# Schematics.net
KiCad netlist of a schematic drawn in Altium Designer
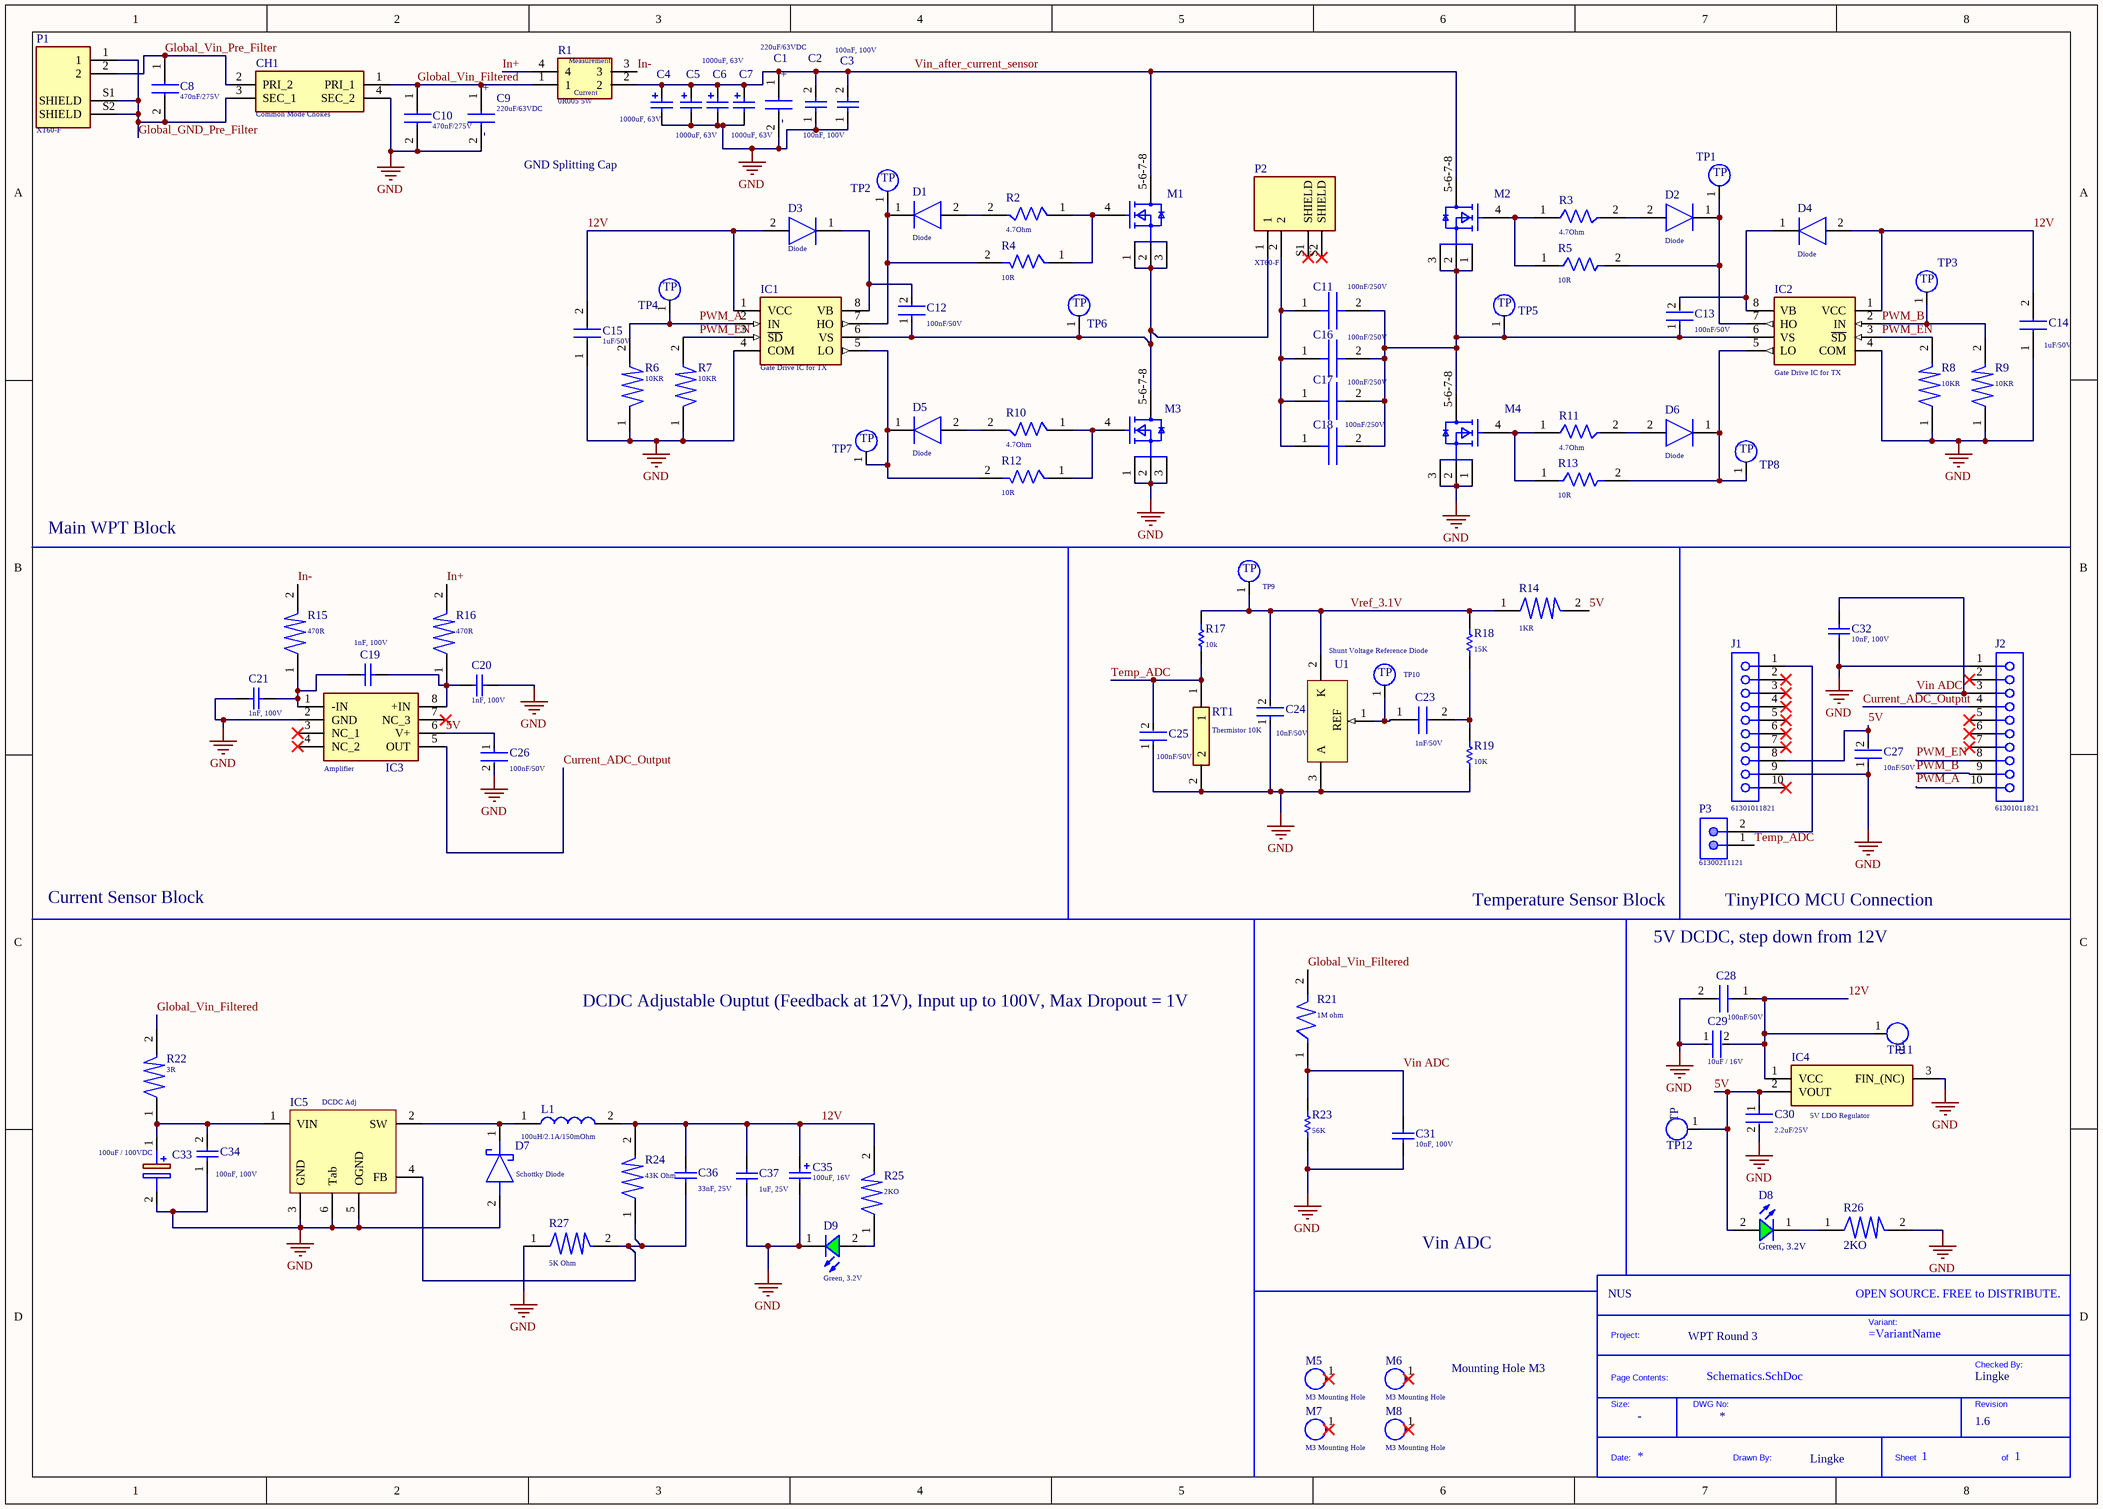
[diagram p0: Schematics.SchDoc]

(export (version "E")
  (design (tool "Eeschema 10.0.6"))
  (components
    (comp (ref "*1")
      (value "Title_Block")
      (description "Standard Title Block.")
      (fields
        (field (name "PROJECT NAME") "WPT Round 3")
        (field (name "COMPANY") "NUS")
        (field (name "DRAWN BY") "Lingke")
        (field (name "REVISION") "1.6")
        (field (name "DWG NO") "*")
        (field (name "SIZE") "-")
        (field (name "CHECKED BY") "Lingke")
      )
      (libsource (lib "Symbol Library") (part "Title_Block"))
    )
    (comp (ref "C1")
      (value "220uF/63VDC")
      (footprint "SamacSys:CAPPRD500W62D1000H2650")
      (description "Polarised Cap, 220uF/63VDC")
      (fields (field (name "MANUFACTURER_PART_NUMBER") "860040775010"))
      (libsource (lib "Symbol Library") (part "860040775010"))
    )
    (comp (ref "C2")
      (value "100nF, 100V")
      (footprint "WCAP-CSGP_0805_H=1.25mm")
      (description "WCAP-CSGP Multilayer Ceramic Chip Capacitor, General Purpose, size 0805, X7R, 100nF, 100V")
      (fields
        (field (name "MANUFACTURER PART NUMBER") "885012207128")
        (field (name "MANUFACTURER") "Wurth Elektronik")
      )
      (libsource (lib "Symbol Library") (part "885012207128"))
    )
    (comp (ref "C3")
      (value "100nF, 100V")
      (footprint "WCAP-CSGP_0805_H=1.25mm")
      (description "WCAP-CSGP Multilayer Ceramic Chip Capacitor, General Purpose, size 0805, X7R, 100nF, 100V")
      (fields
        (field (name "MANUFACTURER PART NUMBER") "885012207128")
        (field (name "MANUFACTURER") "Wurth Elektronik")
      )
      (libsource (lib "Symbol Library") (part "885012207128"))
    )
    (comp (ref "C4")
      (value "1000uF, 63V")
      (footprint "WCAP-ATG8_D16H25")
      (description "WCAP-ATG8 Aluminum Electrolytic Capacitor, Radial, THT, D16xH25, 1000uF, 63V")
      (fields
        (field (name "MANUFACTURER PART NUMBER") "860010780024")
        (field (name "MANUFACTURER") "Wurth Elektronik")
      )
      (libsource (lib "Altium_WCAP-ATG8 (rev20b)") (part "860010780024"))
    )
    (comp (ref "C5")
      (value "1000uF, 63V")
      (footprint "WCAP-ATG8_D16H25")
      (description "WCAP-ATG8 Aluminum Electrolytic Capacitor, Radial, THT, D16xH25, 1000uF, 63V")
      (fields
        (field (name "MANUFACTURER PART NUMBER") "860010780024")
        (field (name "MANUFACTURER") "Wurth Elektronik")
      )
      (libsource (lib "Altium_WCAP-ATG8 (rev20b)") (part "860010780024"))
    )
    (comp (ref "C6")
      (value "1000uF, 63V")
      (footprint "WCAP-ATG8_D16H25")
      (description "WCAP-ATG8 Aluminum Electrolytic Capacitor, Radial, THT, D16xH25, 1000uF, 63V")
      (fields
        (field (name "MANUFACTURER PART NUMBER") "860010780024")
        (field (name "MANUFACTURER") "Wurth Elektronik")
      )
      (libsource (lib "Altium_WCAP-ATG8 (rev20b)") (part "860010780024"))
    )
    (comp (ref "C7")
      (value "1000uF, 63V")
      (footprint "WCAP-ATG8_D16H25")
      (description "WCAP-ATG8 Aluminum Electrolytic Capacitor, Radial, THT, D16xH25, 1000uF, 63V")
      (fields
        (field (name "MANUFACTURER PART NUMBER") "860010780024")
        (field (name "MANUFACTURER") "Wurth Elektronik")
      )
      (libsource (lib "Altium_WCAP-ATG8 (rev20b)") (part "860010780024"))
    )
    (comp (ref "C8")
      (value "470nF/275V")
      (footprint "SamacSys:890324025039CS")
      (description "Safety Capacitor, 470nF/275V")
      (fields (field (name "MANUFACTURER_PART_NUMBER") "890324025039CS"))
      (libsource (lib "Symbol Library") (part "890324025039CS"))
    )
    (comp (ref "C9")
      (value "220uF/63VDC")
      (footprint "SamacSys:CAPPRD500W62D1000H2650")
      (description "Polarised Cap, 220uF/63VDC")
      (fields (field (name "MANUFACTURER_PART_NUMBER") "860040775010"))
      (libsource (lib "Symbol Library") (part "860040775010"))
    )
    (comp (ref "C10")
      (value "470nF/275V")
      (footprint "SamacSys:890324025039CS")
      (description "Safety Capacitor, 470nF/275V")
      (fields (field (name "MANUFACTURER_PART_NUMBER") "890324025039CS"))
      (libsource (lib "Symbol Library") (part "890324025039CS"))
    )
    (comp (ref "C11")
      (value "100nF/250V")
      (footprint "SamacSys:CAPC4532X220N")
      (fields (field (name "MANUFACTURER_PART_NUMBER") "C1812C104JAGACAUTO"))
      (libsource (lib "Symbol Library") (part "C1812C104JAGACAUTO"))
    )
    (comp (ref "C12")
      (value "100nF/50V")
      (footprint "0805 Capacitor")
      (libsource (lib "Symbol Library") (part "885012207098"))
    )
    (comp (ref "C13")
      (value "100nF/50V")
      (footprint "0805 Capacitor")
      (libsource (lib "Symbol Library") (part "885012207098"))
    )
    (comp (ref "C14")
      (value "1uF/50V")
      (footprint "SamacSys:CAPC2012X135N")
      (description "Capacitor 1uF/50V")
      (fields (field (name "MANUFACTURER_PART_NUMBER") "885012207103"))
      (libsource (lib "Symbol Library") (part "885012207103"))
    )
    (comp (ref "C15")
      (value "1uF/50V")
      (footprint "SamacSys:CAPC2012X135N")
      (description "Capacitor 1uF/50V")
      (fields (field (name "MANUFACTURER_PART_NUMBER") "885012207103"))
      (libsource (lib "Symbol Library") (part "885012207103"))
    )
    (comp (ref "C16")
      (value "100nF/250V")
      (footprint "SamacSys:CAPC4532X220N")
      (fields (field (name "MANUFACTURER_PART_NUMBER") "C1812C104JAGACAUTO"))
      (libsource (lib "Symbol Library") (part "C1812C104JAGACAUTO"))
    )
    (comp (ref "C17")
      (value "100nF/250V")
      (footprint "SamacSys:CAPC4532X220N")
      (fields (field (name "MANUFACTURER_PART_NUMBER") "C1812C104JAGACAUTO"))
      (libsource (lib "Symbol Library") (part "C1812C104JAGACAUTO"))
    )
    (comp (ref "C18")
      (value "100nF/250V")
      (footprint "SamacSys:CAPC4532X220N")
      (fields (field (name "MANUFACTURER_PART_NUMBER") "C1812C104JAGACAUTO"))
      (libsource (lib "Symbol Library") (part "C1812C104JAGACAUTO"))
    )
    (comp (ref "C19")
      (value "1nF, 100V")
      (footprint "WCAP-CSGP_0805_H=0.8mm_Reflow")
      (description "WCAP-CSGP Multilayer Ceramic Chip Capacitor, General Purpose, size 0805, X7R, 1nF, 100V")
      (fields
        (field (name "MANUFACTURER PART NUMBER") "885012207116")
        (field (name "MANUFACTURER") "Wurth Elektronik")
      )
      (libsource (lib "Altium_WCAP-CSGP (rev21d)") (part "885012207116"))
    )
    (comp (ref "C20")
      (value "1nF, 100V")
      (footprint "WCAP-CSGP_0805_H=0.8mm_Reflow")
      (description "WCAP-CSGP Multilayer Ceramic Chip Capacitor, General Purpose, size 0805, X7R, 1nF, 100V")
      (fields
        (field (name "MANUFACTURER PART NUMBER") "885012207116")
        (field (name "MANUFACTURER") "Wurth Elektronik")
      )
      (libsource (lib "Altium_WCAP-CSGP (rev21d)") (part "885012207116"))
    )
    (comp (ref "C21")
      (value "1nF, 100V")
      (footprint "WCAP-CSGP_0805_H=0.8mm_Reflow")
      (description "WCAP-CSGP Multilayer Ceramic Chip Capacitor, General Purpose, size 0805, X7R, 1nF, 100V")
      (fields
        (field (name "MANUFACTURER PART NUMBER") "885012207116")
        (field (name "MANUFACTURER") "Wurth Elektronik")
      )
      (libsource (lib "Altium_WCAP-CSGP (rev21d)") (part "885012207116"))
    )
    (comp (ref "C23")
      (value "1nF/50V")
      (footprint "SamacSys:CAPC2012X90N")
      (fields (field (name "MANUFACTURER_PART_NUMBER") "885012207086"))
      (libsource (lib "Symbol Library") (part "885012207086"))
    )
    (comp (ref "C24")
      (value "10nF/50V")
      (footprint "0805 Capacitor")
      (libsource (lib "Symbol Library") (part "885012207092"))
    )
    (comp (ref "C25")
      (value "100nF/50V")
      (footprint "0805 Capacitor")
      (libsource (lib "Symbol Library") (part "885012207098"))
    )
    (comp (ref "C26")
      (value "100nF/50V")
      (footprint "0805 Capacitor")
      (libsource (lib "Symbol Library") (part "885012207098"))
    )
    (comp (ref "C27")
      (value "10nF/50V")
      (footprint "0805 Capacitor")
      (libsource (lib "Symbol Library") (part "885012207092"))
    )
    (comp (ref "C28")
      (value "100nF/50V")
      (footprint "SamacSys:CAPC2012X90N")
      (libsource (lib "") (part "885012207098_1"))
    )
    (comp (ref "C29")
      (value "10uF / 16V")
      (footprint "0805 Capacitor")
      (description "100nF/50V")
      (libsource (lib "WPT NUS") (part "CL21A106KOQNNNE"))
    )
    (comp (ref "C30")
      (value "2.2uF/25V")
      (footprint "0805 Capacitor")
      (libsource (lib "Symbol Library") (part "885012207079"))
    )
    (comp (ref "C31")
      (value "10nF, 100V")
      (footprint "WCAP-CSGP_0805_H=0.8mm_Reflow")
      (description "WCAP-CSGP Multilayer Ceramic Chip Capacitor, General Purpose, size 0805, X7R, 10nF, 100V")
      (fields
        (field (name "MANUFACTURER PART NUMBER") "885012207122")
        (field (name "MANUFACTURER") "Wurth Elektronik")
      )
      (libsource (lib "Altium_WCAP-CSGP (rev21d)") (part "885012207122"))
    )
    (comp (ref "C32")
      (value "10nF, 100V")
      (footprint "WCAP-CSGP_0805_H=0.8mm_Reflow")
      (description "WCAP-CSGP Multilayer Ceramic Chip Capacitor, General Purpose, size 0805, X7R, 10nF, 100V")
      (fields
        (field (name "MANUFACTURER PART NUMBER") "885012207122")
        (field (name "MANUFACTURER") "Wurth Elektronik")
      )
      (libsource (lib "Altium_WCAP-CSGP (rev21d)") (part "885012207122"))
    )
    (comp (ref "C33")
      (value "100uF / 100VDC")
      (footprint "CAPPRD500W60D1000H2200")
      (description "Capacitor Polarised")
      (fields
        (field (name "MANUFACTURER_PART_NUMBER") "ESH107M100AH4AA")
        (field (name "MOUSER PART NUMBER") "80-ESH107M100AH4AA")
      )
      (libsource (lib "WPT NUS") (part "ESH107M100AH4AA"))
    )
    (comp (ref "C34")
      (value "100nF, 100V")
      (footprint "WCAP-CSGP_0805_H=1.25mm")
      (description "WCAP-CSGP Multilayer Ceramic Chip Capacitor, General Purpose, size 0805, X7R, 100nF, 100V")
      (fields
        (field (name "MANUFACTURER PART NUMBER") "885012207128")
        (field (name "MANUFACTURER") "Wurth Elektronik")
      )
      (libsource (lib "Symbol Library") (part "885012207128"))
    )
    (comp (ref "C35")
      (value "100uF, 16V")
      (footprint "WCAP-ASLI_D6.3H5.5")
      (description "WCAP-ASLI Aluminum Electrolytic Capacitor, V-Chip, SMT, D6.3xH5.5mm, 100uF, 16V")
      (fields
        (field (name "MANUFACTURER PART NUMBER") "865080343009")
        (field (name "MANUFACTURER") "Wurth Elektronik")
      )
      (libsource (lib "Altium_WCAP-ASLI (rev20b) (1)") (part "865080343009"))
    )
    (comp (ref "C36")
      (value "33nF, 25V")
      (footprint "WCAP-CSGP_0805_H=0.8mm_Reflow")
      (description "WCAP-CSGP Multilayer Ceramic Chip Capacitor, General Purpose, size 0805, X7R, 33nF, 25V")
      (fields
        (field (name "MANUFACTURER PART NUMBER") "885012207069")
        (field (name "MANUFACTURER") "Wurth Elektronik")
      )
      (libsource (lib "Altium_WCAP-CSGP (rev21d)") (part "885012207069"))
    )
    (comp (ref "C37")
      (value "1uF, 25V")
      (footprint "WCAP-CSGP_0805_H=1.25mm")
      (description "WCAP-CSGP Multilayer Ceramic Chip Capacitor, General Purpose, size 0805, X7R, 1uF, 25V")
      (fields
        (field (name "MANUFACTURER PART NUMBER") "885012207078")
        (field (name "MANUFACTURER") "Wurth Elektronik")
      )
      (libsource (lib "Altium_WCAP-CSGP (rev21d)") (part "885012207078"))
    )
    (comp (ref "CH1")
      (value "Common Mode Chokes")
      (footprint "SamacSys:PA5141205NLT")
      (description "Filter")
      (fields
        (field (name "MANUFACTURER_PART_NUMBER") "PA5141.205NLT")
        (field (name "MOUSER PART NUMBER") "673-PA5141.205NLT")
      )
      (libsource (lib "Symbol Library") (part "PA5141.205NLT"))
    )
    (comp (ref "D1")
      (value "Diode")
      (footprint "SamacSys:SOD3716X135N")
      (fields
        (field (name "MOUSER2 PART NUMBER") "78-1N4148W-E3-08")
        (field (name "MANUFACTURER_PART_NUMBER") "1N4148W-E3-08")
      )
      (libsource (lib "Symbol Library") (part "1N4148W-E3-08"))
    )
    (comp (ref "D2")
      (value "Diode")
      (footprint "SamacSys:SOD3716X135N")
      (fields
        (field (name "MOUSER2 PART NUMBER") "78-1N4148W-E3-08")
        (field (name "MANUFACTURER_PART_NUMBER") "1N4148W-E3-08")
      )
      (libsource (lib "Symbol Library") (part "1N4148W-E3-08"))
    )
    (comp (ref "D3")
      (value "Diode")
      (footprint "SamacSys:SOD3716X135N")
      (fields
        (field (name "MOUSER2 PART NUMBER") "78-1N4148W-E3-08")
        (field (name "MANUFACTURER_PART_NUMBER") "1N4148W-E3-08")
      )
      (libsource (lib "Symbol Library") (part "1N4148W-E3-08"))
    )
    (comp (ref "D4")
      (value "Diode")
      (footprint "SamacSys:SOD3716X135N")
      (fields
        (field (name "MOUSER2 PART NUMBER") "78-1N4148W-E3-08")
        (field (name "MANUFACTURER_PART_NUMBER") "1N4148W-E3-08")
      )
      (libsource (lib "Symbol Library") (part "1N4148W-E3-08"))
    )
    (comp (ref "D5")
      (value "Diode")
      (footprint "SamacSys:SOD3716X135N")
      (fields
        (field (name "MOUSER2 PART NUMBER") "78-1N4148W-E3-08")
        (field (name "MANUFACTURER_PART_NUMBER") "1N4148W-E3-08")
      )
      (libsource (lib "Symbol Library") (part "1N4148W-E3-08"))
    )
    (comp (ref "D6")
      (value "Diode")
      (footprint "SamacSys:SOD3716X135N")
      (fields
        (field (name "MOUSER2 PART NUMBER") "78-1N4148W-E3-08")
        (field (name "MANUFACTURER_PART_NUMBER") "1N4148W-E3-08")
      )
      (libsource (lib "Symbol Library") (part "1N4148W-E3-08"))
    )
    (comp (ref "D7")
      (value "Schottky Diode")
      (footprint "SamacSys:DIONM8059X265N")
      (fields (field (name "MANUFACTURER_PART_NUMBER") "S310") (field (name "MOUSER PART NUMBER") "512-S310"))
      (libsource (lib "Symbol Library") (part "S310"))
    )
    (comp (ref "D8")
      (value "Green, 3.2V")
      (footprint "WL-SMCW_0805")
      (description "WL-SMCW SMT Mono-color Chip LED Waterclear, size 0805, Green, 3.2V, 140deg")
      (fields (field (name "PART NUMBER") "150080GS75000") (field (name "PUBLISHER") "Wurth Elektronik"))
      (libsource (lib "Altium_WL-SMCW (rev20a)") (part "150080GS75000"))
    )
    (comp (ref "D9")
      (value "Green, 3.2V")
      (footprint "WL-SMCW_0805")
      (description "WL-SMCW SMT Mono-color Chip LED Waterclear, size 0805, Green, 3.2V, 140deg")
      (fields (field (name "PART NUMBER") "150080GS75000") (field (name "PUBLISHER") "Wurth Elektronik"))
      (libsource (lib "Altium_WL-SMCW (rev20a)") (part "150080GS75000"))
    )
    (comp (ref "IC1")
      (value "Gate Drive IC for TX")
      (footprint "SamacSys:SOIC127P600X175-8N")
      (description "Gate Drive IC")
      (fields (field (name "MANUFACTURER_PART_NUMBER") "IRS2008SPBF"))
      (libsource (lib "") (part "IRS2008SPBF_1"))
    )
    (comp (ref "IC2")
      (value "Gate Drive IC for TX")
      (footprint "SamacSys:SOIC127P600X175-8N")
      (description "Gate Drive IC")
      (fields (field (name "MANUFACTURER_PART_NUMBER") "IRS2008SPBF"))
      (libsource (lib "Symbol Library") (part "IRS2008SPBF"))
    )
    (comp (ref "IC3")
      (value "Amplifier")
      (footprint "SamacSys:SOIC127P600X175-8N")
      (description "Integrated Circuit Amplifier")
      (fields (field (name "MANUFACTURER_PART_NUMBER") "AD8215YRZ"))
      (libsource (lib "Symbol Library") (part "AD8215YRZ"))
    )
    (comp (ref "IC4")
      (value "5V LDO Regulator")
      (footprint "SamacSys:ROHM_TO-252-3")
      (fields
        (field (name "MOUSER2 PART NUMBER") "755-BD450M5FP-CE2")
        (field (name "MANUFACTURER_PART_NUMBER") "BD450M5FP-CE2")
      )
      (libsource (lib "Symbol Library") (part "BD450M5FP-CE2"))
    )
    (comp (ref "IC5")
      (value "DCDC Adj")
      (footprint "TO-263-5")
      (libsource (lib "Symbol Library") (part "XL7035E1"))
    )
    (comp (ref "J1")
      (value "61301011821")
      (footprint "61301011821")
      (description "WR-PHD Socket Header, THT, pitch 2.54mm, Single Row, Vertical, 10p")
      (fields (field (name "MANUFACTURER") "Wurth Elektronik"))
      (libsource (lib "Altium_WR-PHD (rev20a)") (part "61301011821"))
    )
    (comp (ref "J2")
      (value "61301011821")
      (footprint "61301011821")
      (description "WR-PHD Socket Header, THT, pitch 2.54mm, Single Row, Vertical, 10p")
      (fields (field (name "MANUFACTURER") "Wurth Elektronik"))
      (libsource (lib "Altium_WR-PHD (rev20a)") (part "61301011821"))
    )
    (comp (ref "L1")
      (value "100uH/2.1A/150mOhm")
      (footprint "SamacSys:INDPM125125X800N")
      (description "Inductor")
      (fields
        (field (name "MANUFACTURER_PART_NUMBER") "SRR1280-101M")
        (field (name "MOUSER PART NUMBER") "652-SRR1280-101M")
      )
      (libsource (lib "Symbol Library") (part "SRR1280-101M"))
    )
    (comp (ref "M1")
      (value "Mosfet")
      (footprint "FP-PG-TDSON-8-MFG")
      (description "MOSFET N-CH 100V 100A 8TDSON\r\nMosfet Switcher")
      (fields
        (field (name "MANUFACTURER") "Infineon")
        (field (name "MANUFACTURER PART NUMBER") "BSC040N10NS5ATMA1")
      )
      (libsource (lib "Symbol Library") (part "BSC040N10NS5ATMA1"))
    )
    (comp (ref "M2")
      (value "Mosfet")
      (footprint "FP-PG-TDSON-8-MFG")
      (description "MOSFET N-CH 100V 100A 8TDSON\r\nMosfet Switcher")
      (fields
        (field (name "MANUFACTURER") "Infineon")
        (field (name "MANUFACTURER PART NUMBER") "BSC040N10NS5ATMA1")
      )
      (libsource (lib "Symbol Library") (part "BSC040N10NS5ATMA1"))
    )
    (comp (ref "M3")
      (value "Mosfet")
      (footprint "FP-PG-TDSON-8-MFG")
      (description "MOSFET N-CH 100V 100A 8TDSON\r\nMosfet Switcher")
      (fields
        (field (name "MANUFACTURER") "Infineon")
        (field (name "MANUFACTURER PART NUMBER") "BSC040N10NS5ATMA1")
      )
      (libsource (lib "Symbol Library") (part "BSC040N10NS5ATMA1"))
    )
    (comp (ref "M4")
      (value "Mosfet")
      (footprint "FP-PG-TDSON-8-MFG")
      (description "MOSFET N-CH 100V 100A 8TDSON\r\nMosfet Switcher")
      (fields
        (field (name "MANUFACTURER") "Infineon")
        (field (name "MANUFACTURER PART NUMBER") "BSC040N10NS5ATMA1")
      )
      (libsource (lib "Symbol Library") (part "BSC040N10NS5ATMA1"))
    )
    (comp (ref "M5")
      (value "M3 Mounting Hole")
      (footprint "M3 Hole")
      (libsource (lib "Symbol Library") (part "M3_Mounting_hole"))
    )
    (comp (ref "M6")
      (value "M3 Mounting Hole")
      (footprint "M3 Hole")
      (libsource (lib "Symbol Library") (part "M3_Mounting_hole"))
    )
    (comp (ref "M7")
      (value "M3 Mounting Hole")
      (footprint "M3 Hole")
      (libsource (lib "Symbol Library") (part "M3_Mounting_hole"))
    )
    (comp (ref "M8")
      (value "M3 Mounting Hole")
      (footprint "M3 Hole")
      (libsource (lib "Symbol Library") (part "M3_Mounting_hole"))
    )
    (comp (ref "P1")
      (value "XT60-F")
      (footprint "Footprint Library:AMASS_XT60PW-F")
      (description "Socket DC Supply Connector Female")
      (fields (field (name "MP") "XT60PW-F") (field (name "MF") "AMASS"))
      (libsource (lib "Symbol Library") (part "XT60PW-F"))
    )
    (comp (ref "P2")
      (value "XT60-F")
      (footprint "Footprint Library:AMASS_XT60PW-F")
      (description "Socket DC Supply Connector Female")
      (fields (field (name "MP") "XT60PW-F") (field (name "MF") "AMASS"))
      (libsource (lib "") (part "XT60PW-F_1"))
    )
    (comp (ref "P3")
      (value "61300211121")
      (footprint "61300211121")
      (description "WR-PHD Pin Header, THT, pitch 2.54mm, Single Row, Vertical, 2p")
      (fields (field (name "MANUFACTURER") "Wurth Elektronik"))
      (libsource (lib "Altium_WR-PHD (rev20a)") (part "61300211121"))
    )
    (comp (ref "R1")
      (value "0R005 5W")
      (footprint "SamacSys:FC4L110R005FER")
      (description "Resistor 0R005 5W")
      (fields (field (name "MANUFACTURER_PART_NUMBER") "FC4L110R005FER"))
      (libsource (lib "Symbol Library") (part "FC4L110R005FER"))
    )
    (comp (ref "R2")
      (value "4.7Ohm")
      (footprint "FP-CRCW1206-e3-IPC_A")
      (description "RES Thick Film, 4.7Ω, 1%, 0.25W, 100ppm/°C, 1206\r\nMOSFET Gate Fast-off Resistor 4.7Ohm")
      (fields (field (name "TOLERANCE") "1%"))
      (libsource (lib "Symbol Library") (part "CRCW12064R70FKEA"))
    )
    (comp (ref "R3")
      (value "4.7Ohm")
      (footprint "FP-CRCW1206-e3-IPC_A")
      (description "RES Thick Film, 4.7Ω, 1%, 0.25W, 100ppm/°C, 1206\r\nMOSFET Gate Fast-off Resistor 4.7Ohm")
      (fields (field (name "TOLERANCE") "1%"))
      (libsource (lib "Symbol Library") (part "CRCW12064R70FKEA"))
    )
    (comp (ref "R4")
      (value "10R")
      (footprint "FP-CRCW1206-e3-IPC_A")
      (description "RES Thick Film, 10Ω, 1%, 0.25W, 100ppm/°C, 1206\r\nMOSFET Gate Resistor 10Ohm")
      (fields (field (name "TOLERANCE") "1%"))
      (libsource (lib "Symbol Library") (part "CRCW120610R0FKEA"))
    )
    (comp (ref "R5")
      (value "10R")
      (footprint "FP-CRCW1206-e3-IPC_A")
      (description "RES Thick Film, 10Ω, 1%, 0.25W, 100ppm/°C, 1206\r\nMOSFET Gate Resistor 10Ohm")
      (fields (field (name "TOLERANCE") "1%"))
      (libsource (lib "Symbol Library") (part "CRCW120610R0FKEA"))
    )
    (comp (ref "R6")
      (value "10KR")
      (footprint "FP-CRCW0805-e3-MFG")
      (description "Resistor 10K Ohm")
      (libsource (lib "Symbol Library") (part "CRCW080510K0FKEA"))
    )
    (comp (ref "R7")
      (value "10KR")
      (footprint "FP-CRCW0805-e3-MFG")
      (description "Resistor 10K Ohm")
      (libsource (lib "Symbol Library") (part "CRCW080510K0FKEA"))
    )
    (comp (ref "R8")
      (value "10KR")
      (footprint "FP-CRCW0805-e3-MFG")
      (description "Resistor 10K Ohm")
      (libsource (lib "Symbol Library") (part "CRCW080510K0FKEA"))
    )
    (comp (ref "R9")
      (value "10KR")
      (footprint "FP-CRCW0805-e3-MFG")
      (description "Resistor 10K Ohm")
      (libsource (lib "Symbol Library") (part "CRCW080510K0FKEA"))
    )
    (comp (ref "R10")
      (value "4.7Ohm")
      (footprint "FP-CRCW1206-e3-IPC_A")
      (description "RES Thick Film, 4.7Ω, 1%, 0.25W, 100ppm/°C, 1206\r\nMOSFET Gate Fast-off Resistor 4.7Ohm")
      (fields (field (name "TOLERANCE") "1%"))
      (libsource (lib "Symbol Library") (part "CRCW12064R70FKEA"))
    )
    (comp (ref "R11")
      (value "4.7Ohm")
      (footprint "FP-CRCW1206-e3-IPC_A")
      (description "RES Thick Film, 4.7Ω, 1%, 0.25W, 100ppm/°C, 1206\r\nMOSFET Gate Fast-off Resistor 4.7Ohm")
      (fields (field (name "TOLERANCE") "1%"))
      (libsource (lib "Symbol Library") (part "CRCW12064R70FKEA"))
    )
    (comp (ref "R12")
      (value "10R")
      (footprint "FP-CRCW1206-e3-IPC_A")
      (description "RES Thick Film, 10Ω, 1%, 0.25W, 100ppm/°C, 1206\r\nMOSFET Gate Resistor 10Ohm")
      (fields (field (name "TOLERANCE") "1%"))
      (libsource (lib "Symbol Library") (part "CRCW120610R0FKEA"))
    )
    (comp (ref "R13")
      (value "10R")
      (footprint "FP-CRCW1206-e3-IPC_A")
      (description "RES Thick Film, 10Ω, 1%, 0.25W, 100ppm/°C, 1206\r\nMOSFET Gate Resistor 10Ohm")
      (fields (field (name "TOLERANCE") "1%"))
      (libsource (lib "Symbol Library") (part "CRCW120610R0FKEA"))
    )
    (comp (ref "R14")
      (value "1KR")
      (footprint "FP-CRCW0805-e3-MFG")
      (description "Resistor 1k Ohm")
      (libsource (lib "Symbol Library") (part "CRCW08051K00FKEA"))
    )
    (comp (ref "R15")
      (value "470R")
      (footprint "FP-CRCW0805-e3-MFG")
      (description "Resistor 470 Ohm")
      (libsource (lib "Symbol Library") (part "CRCW0805470RFKEB"))
    )
    (comp (ref "R16")
      (value "470R")
      (footprint "FP-CRCW0805-e3-MFG")
      (description "Resistor 470 Ohm")
      (libsource (lib "Symbol Library") (part "CRCW0805470RFKEB"))
    )
    (comp (ref "R17")
      (value "10k")
      (footprint "0805 Resistor")
      (description "High Presition and High reliability 10K Ohm Resistor")
      (libsource (lib "Symbol Library") (part "ERA-6ARB103V"))
    )
    (comp (ref "R18")
      (value "15K")
      (footprint "0805 Resistor")
      (description "High Presicion 15K Ohm")
      (libsource (lib "Symbol Library") (part "ERA-6ARW153V"))
    )
    (comp (ref "R19")
      (value "10K")
      (footprint "0805 Resistor")
      (description "High Presicion 10K Ohm")
      (libsource (lib "Symbol Library") (part "CRCW080510K0FKEB"))
    )
    (comp (ref "R21")
      (value "1M ohm")
      (footprint "FP-CRCW0805-e3-MFG")
      (description "RES Thick Film, 1MΩ, 1%, 0.125W, 100ppm/°C, 0805\r\n1M Ohm Resistor")
      (fields (field (name "TOLERANCE") "1%"))
      (libsource (lib "Symbol Library") (part "CRCW08051M00FKEA"))
    )
    (comp (ref "R22")
      (value "3R")
      (footprint "1206_Resistor")
      (description "Resistor 3 Ohm")
      (libsource (lib "WPT NUS") (part "CRCW12063R00FKEAHP"))
    )
    (comp (ref "R23")
      (value "56K")
      (footprint "0805 Resistor")
      (description "56K Ohm Resistor")
      (libsource (lib "Symbol Library") (part "ERJ-6ENF5622V"))
    )
    (comp (ref "R24")
      (value "43K Ohm")
      (footprint "FP-CRCW0805-e3-MFG")
      (description "Resistor 43K Ohm")
      (libsource (lib "Symbol Library") (part "RC0805FR-0743KL"))
    )
    (comp (ref "R25")
      (value "2KO")
      (footprint "FP-CRCW0805-e3-MFG")
      (description "RES Thick Film, 2kΩ, 1%, 0.125W, 100ppm/°C, 0805")
      (fields (field (name "TOLERANCE") "1%"))
      (libsource (lib "Symbol Library") (part "CRCW08052K00FKEB"))
    )
    (comp (ref "R26")
      (value "2KO")
      (footprint "FP-CRCW0805-e3-MFG")
      (description "RES Thick Film, 2kΩ, 1%, 0.125W, 100ppm/°C, 0805")
      (fields (field (name "TOLERANCE") "1%"))
      (libsource (lib "Symbol Library") (part "CRCW08052K00FKEB"))
    )
    (comp (ref "R27")
      (value "5K Ohm")
      (footprint "FP-CRCW0805-e3-MFG")
      (description "Resistor 5K Ohm")
      (libsource (lib "Symbol Library") (part "CRCW08055K00FKTA"))
    )
    (comp (ref "RT1")
      (value "Thermistor 10K")
      (footprint "SamacSys:THRMC2012X95N")
      (description "Thermistor 10Kohm B Parameter: 3950k")
      (fields (field (name "MANUFACTURER_PART_NUMBER") "NTCS0805E3103HMT"))
      (libsource (lib "Symbol Library") (part "NTCS0805E3103HMT"))
    )
    (comp (ref "TP1")
      (value "TP")
      (footprint "Test Point")
      (description "Test Point 1mm by 1mm")
      (libsource (lib "Symbol Library") (part "Test Point"))
    )
    (comp (ref "TP2")
      (value "TP")
      (footprint "Test Point")
      (description "Test Point 1mm by 1mm")
      (libsource (lib "Symbol Library") (part "Test Point"))
    )
    (comp (ref "TP3")
      (value "TP")
      (footprint "Test Point")
      (description "Test Point 1mm by 1mm")
      (libsource (lib "Symbol Library") (part "Test Point"))
    )
    (comp (ref "TP4")
      (value "TP")
      (footprint "Test Point")
      (description "Test Point 1mm by 1mm")
      (libsource (lib "Symbol Library") (part "Test Point"))
    )
    (comp (ref "TP5")
      (value "TP")
      (footprint "Test Point")
      (description "Test Point 1mm by 1mm")
      (libsource (lib "Symbol Library") (part "Test Point"))
    )
    (comp (ref "TP6")
      (value "TP")
      (footprint "Test Point")
      (description "Test Point 1mm by 1mm")
      (libsource (lib "Symbol Library") (part "Test Point"))
    )
    (comp (ref "TP7")
      (value "TP")
      (footprint "Test Point")
      (description "Test Point 1mm by 1mm")
      (libsource (lib "Symbol Library") (part "Test Point"))
    )
    (comp (ref "TP8")
      (value "TP")
      (footprint "Test Point")
      (description "Test Point 1mm by 1mm")
      (libsource (lib "Symbol Library") (part "Test Point"))
    )
    (comp (ref "TP9")
      (value "TP")
      (footprint "Test Point")
      (description "Test Point 1mm by 1mm")
      (libsource (lib "Symbol Library") (part "Test Point"))
    )
    (comp (ref "TP10")
      (value "TP")
      (footprint "Test Point")
      (description "Test Point 1mm by 1mm")
      (libsource (lib "Symbol Library") (part "Test Point"))
    )
    (comp (ref "TP11")
      (value "TP")
      (footprint "Test Point")
      (description "Test Point 1mm by 1mm")
      (libsource (lib "Symbol Library") (part "Test Point"))
    )
    (comp (ref "TP12")
      (value "TP")
      (footprint "Test Point")
      (description "Test Point 1mm by 1mm")
      (libsource (lib "Symbol Library") (part "Test Point"))
    )
    (comp (ref "U1")
      (value "Shunt Voltage Reference Diode")
      (footprint "SOT23-3_N")
      (description "Shunt voltage reference, adjustable, 1.24 to 10V, 0.5% precision, 3-Pin SOT23-3L, Tape and Reel")
      (libsource (lib "Symbol Library") (part "TS432AILT"))
    )
  )
  (nets
    (net (code "1") (name "/5V") (class "Default")
      (node (ref "C26") (pin "1") (pinfunction "1_1") (pintype "passive"))
      (node (ref "C27") (pin "2") (pinfunction "2_2") (pintype "passive"))
      (node (ref "C30") (pin "1") (pinfunction "1_1") (pintype "passive"))
      (node (ref "D8") (pin "2") (pinfunction "A_2") (pintype "passive"))
      (node (ref "IC3") (pin "6") (pinfunction "V+_6") (pintype "passive"))
      (node (ref "IC4") (pin "2") (pinfunction "VOUT_2") (pintype "passive"))
      (node (ref "J1") (pin "8") (pinfunction "8_8") (pintype "passive"))
      (node (ref "R14") (pin "2") (pinfunction "2_2") (pintype "passive"))
      (node (ref "TP12") (pin "1") (pinfunction "TP_1") (pintype "passive"))
    )
    (net (code "2") (name "/12V") (class "Default")
      (node (ref "C14") (pin "2") (pinfunction "2_2") (pintype "passive"))
      (node (ref "C15") (pin "2") (pinfunction "2_2") (pintype "passive"))
      (node (ref "C28") (pin "1") (pinfunction "1_1") (pintype "passive"))
      (node (ref "C29") (pin "2") (pinfunction "2_2") (pintype "passive"))
      (node (ref "C35") (pin "1") (pinfunction "P_1") (pintype "passive"))
      (node (ref "C36") (pin "2") (pinfunction "2_2") (pintype "passive"))
      (node (ref "C37") (pin "2") (pinfunction "2_2") (pintype "passive"))
      (node (ref "D3") (pin "2") (pinfunction "A_2") (pintype "passive"))
      (node (ref "D4") (pin "2") (pinfunction "A_2") (pintype "passive"))
      (node (ref "IC1") (pin "1") (pinfunction "VCC_1") (pintype "power_in"))
      (node (ref "IC2") (pin "1") (pinfunction "VCC_1") (pintype "power_in"))
      (node (ref "IC4") (pin "1") (pinfunction "VCC_1") (pintype "passive"))
      (node (ref "L1") (pin "2") (pinfunction "2_2") (pintype "passive"))
      (node (ref "R24") (pin "2") (pinfunction "2_2") (pintype "passive"))
      (node (ref "R25") (pin "2") (pinfunction "2_2") (pintype "passive"))
      (node (ref "TP11") (pin "1") (pinfunction "TP_1") (pintype "passive"))
    )
    (net (code "3") (name "/Current_ADC_Output") (class "Default")
      (node (ref "IC3") (pin "5") (pinfunction "OUT_5") (pintype "passive"))
      (node (ref "J2") (pin "4") (pinfunction "4_4") (pintype "passive"))
    )
    (net (code "4") (name "/Global_GND_Pre_Filter") (class "Default")
      (node (ref "C8") (pin "2") (pinfunction "2_2") (pintype "passive"))
      (node (ref "CH1") (pin "3") (pinfunction "SEC_1_3") (pintype "passive"))
      (node (ref "P1") (pin "1") (pinfunction "1_1") (pintype "passive"))
      (node (ref "P1") (pin "S1") (pinfunction "SHIELD_S1") (pintype "passive"))
      (node (ref "P1") (pin "S2") (pinfunction "SHIELD_S2") (pintype "passive"))
    )
    (net (code "5") (name "/Global_Vin_Filtered") (class "Default")
      (node (ref "C10") (pin "1") (pinfunction "1_1") (pintype "passive"))
      (node (ref "C9") (pin "1") (pinfunction "+_1") (pintype "passive"))
      (node (ref "CH1") (pin "1") (pinfunction "PRI_1_1") (pintype "passive"))
      (node (ref "R1") (pin "1") (pinfunction "1_1") (pintype "passive"))
      (node (ref "R21") (pin "2") (pinfunction "2_2") (pintype "passive"))
      (node (ref "R22") (pin "2") (pinfunction "2_2") (pintype "passive"))
    )
    (net (code "6") (name "/Global_Vin_Pre_Filter") (class "Default")
      (node (ref "C8") (pin "1") (pinfunction "1_1") (pintype "passive"))
      (node (ref "CH1") (pin "2") (pinfunction "PRI_2_2") (pintype "passive"))
      (node (ref "P1") (pin "2") (pinfunction "2_2") (pintype "passive"))
    )
    (net (code "7") (name "/In+") (class "Default")
      (node (ref "R1") (pin "4") (pinfunction "4_4") (pintype "passive"))
      (node (ref "R16") (pin "2") (pinfunction "2_2") (pintype "passive"))
    )
    (net (code "8") (name "/In-") (class "Default")
      (node (ref "R1") (pin "3") (pinfunction "3_3") (pintype "passive"))
      (node (ref "R15") (pin "2") (pinfunction "2_2") (pintype "passive"))
    )
    (net (code "9") (name "/PWM_A") (class "Default")
      (node (ref "IC1") (pin "2") (pinfunction "IN_2") (pintype "input"))
      (node (ref "J2") (pin "10") (pinfunction "10_10") (pintype "passive"))
      (node (ref "R6") (pin "2") (pinfunction "2_2") (pintype "passive"))
      (node (ref "TP4") (pin "1") (pinfunction "TP_1") (pintype "passive"))
    )
    (net (code "10") (name "/PWM_B") (class "Default")
      (node (ref "IC2") (pin "2") (pinfunction "IN_2") (pintype "input"))
      (node (ref "J2") (pin "9") (pinfunction "9_9") (pintype "passive"))
      (node (ref "R9") (pin "2") (pinfunction "2_2") (pintype "passive"))
      (node (ref "TP3") (pin "1") (pinfunction "TP_1") (pintype "passive"))
    )
    (net (code "11") (name "/PWM_EN") (class "Default")
      (node (ref "IC1") (pin "3") (pinfunction "~{SD}_3") (pintype "input"))
      (node (ref "IC2") (pin "3") (pinfunction "~{SD}_3") (pintype "input"))
      (node (ref "J2") (pin "8") (pinfunction "8_8") (pintype "passive"))
      (node (ref "R7") (pin "2") (pinfunction "2_2") (pintype "passive"))
      (node (ref "R8") (pin "2") (pinfunction "2_2") (pintype "passive"))
    )
    (net (code "12") (name "/Temp_ADC") (class "Default")
      (node (ref "C25") (pin "2") (pinfunction "2_2") (pintype "passive"))
      (node (ref "P3") (pin "1") (pinfunction "1_1") (pintype "passive"))
      (node (ref "R17") (pin "1") (pinfunction "1_1") (pintype "passive"))
      (node (ref "RT1") (pin "1") (pinfunction "1_1") (pintype "passive"))
    )
    (net (code "13") (name "/Vin ADC") (class "Default")
      (node (ref "C31") (pin "2") (pinfunction "2_2") (pintype "passive"))
      (node (ref "C32") (pin "2") (pinfunction "2_2") (pintype "passive"))
      (node (ref "J2") (pin "3") (pinfunction "3_3") (pintype "passive"))
      (node (ref "R21") (pin "1") (pinfunction "1_1") (pintype "passive"))
      (node (ref "R23") (pin "2") (pinfunction "2_2") (pintype "passive"))
    )
    (net (code "14") (name "/Vin_after_current_sensor") (class "Default")
      (node (ref "C1") (pin "1") (pinfunction "+_1") (pintype "passive"))
      (node (ref "C2") (pin "2") (pinfunction "2_2") (pintype "passive"))
      (node (ref "C3") (pin "2") (pinfunction "2_2") (pintype "passive"))
      (node (ref "C4") (pin "1") (pinfunction "P_1") (pintype "passive"))
      (node (ref "C5") (pin "1") (pinfunction "P_1") (pintype "passive"))
      (node (ref "C6") (pin "1") (pinfunction "P_1") (pintype "passive"))
      (node (ref "C7") (pin "1") (pinfunction "P_1") (pintype "passive"))
      (node (ref "M1") (pin "5-6-7-8") (pinfunction "D_5-6-7-8") (pintype "passive"))
      (node (ref "M2") (pin "5-6-7-8") (pinfunction "D_5-6-7-8") (pintype "passive"))
      (node (ref "R1") (pin "2") (pinfunction "2_2") (pintype "passive"))
    )
    (net (code "15") (name "/Vref_3.1V") (class "Default")
      (node (ref "C24") (pin "2") (pinfunction "2_2") (pintype "passive"))
      (node (ref "R14") (pin "1") (pinfunction "1_1") (pintype "passive"))
      (node (ref "R17") (pin "2") (pinfunction "2_2") (pintype "passive"))
      (node (ref "R18") (pin "2") (pinfunction "2_2") (pintype "passive"))
      (node (ref "TP9") (pin "1") (pinfunction "TP_1") (pintype "passive"))
      (node (ref "U1") (pin "2") (pinfunction "K_2") (pintype "passive"))
    )
    (net (code "16") (name "GND") (class "Default")
      (node (ref "C1") (pin "2") (pinfunction "-_2") (pintype "passive"))
      (node (ref "C10") (pin "2") (pinfunction "2_2") (pintype "passive"))
      (node (ref "C14") (pin "1") (pinfunction "1_1") (pintype "passive"))
      (node (ref "C15") (pin "1") (pinfunction "1_1") (pintype "passive"))
      (node (ref "C2") (pin "1") (pinfunction "1_1") (pintype "passive"))
      (node (ref "C20") (pin "2") (pinfunction "2_2") (pintype "passive"))
      (node (ref "C21") (pin "1") (pinfunction "1_1") (pintype "passive"))
      (node (ref "C24") (pin "1") (pinfunction "1_1") (pintype "passive"))
      (node (ref "C25") (pin "1") (pinfunction "1_1") (pintype "passive"))
      (node (ref "C26") (pin "2") (pinfunction "2_2") (pintype "passive"))
      (node (ref "C27") (pin "1") (pinfunction "1_1") (pintype "passive"))
      (node (ref "C28") (pin "2") (pinfunction "2_2") (pintype "passive"))
      (node (ref "C29") (pin "1") (pinfunction "1_1") (pintype "passive"))
      (node (ref "C3") (pin "1") (pinfunction "1_1") (pintype "passive"))
      (node (ref "C30") (pin "2") (pinfunction "2_2") (pintype "passive"))
      (node (ref "C31") (pin "1") (pinfunction "1_1") (pintype "passive"))
      (node (ref "C32") (pin "1") (pinfunction "1_1") (pintype "passive"))
      (node (ref "C33") (pin "2") (pinfunction "-_2") (pintype "passive"))
      (node (ref "C34") (pin "1") (pinfunction "1_1") (pintype "passive"))
      (node (ref "C35") (pin "2") (pinfunction "N_2") (pintype "passive"))
      (node (ref "C37") (pin "1") (pinfunction "1_1") (pintype "passive"))
      (node (ref "C4") (pin "2") (pinfunction "N_2") (pintype "passive"))
      (node (ref "C5") (pin "2") (pinfunction "N_2") (pintype "passive"))
      (node (ref "C6") (pin "2") (pinfunction "N_2") (pintype "passive"))
      (node (ref "C7") (pin "2") (pinfunction "N_2") (pintype "passive"))
      (node (ref "C9") (pin "2") (pinfunction "-_2") (pintype "passive"))
      (node (ref "CH1") (pin "4") (pinfunction "SEC_2_4") (pintype "passive"))
      (node (ref "D7") (pin "2") (pinfunction "A_2") (pintype "passive"))
      (node (ref "D9") (pin "1") (pinfunction "K_1") (pintype "passive"))
      (node (ref "IC1") (pin "4") (pinfunction "COM_4") (pintype "power_in"))
      (node (ref "IC2") (pin "4") (pinfunction "COM_4") (pintype "power_in"))
      (node (ref "IC3") (pin "2") (pinfunction "GND_2") (pintype "passive"))
      (node (ref "IC4") (pin "3") (pinfunction "FIN_(NC)_3") (pintype "passive"))
      (node (ref "IC5") (pin "3") (pinfunction "GND_3") (pintype "passive"))
      (node (ref "IC5") (pin "5") (pinfunction "OGND_5") (pintype "passive"))
      (node (ref "IC5") (pin "6") (pinfunction "Tab_6") (pintype "passive"))
      (node (ref "J1") (pin "9") (pinfunction "9_9") (pintype "passive"))
      (node (ref "J2") (pin "1") (pinfunction "1_1") (pintype "passive"))
      (node (ref "M3") (pin "1") (pinfunction "S_1") (pintype "passive"))
      (node (ref "M3") (pin "2") (pinfunction "S_2") (pintype "passive"))
      (node (ref "M3") (pin "3") (pinfunction "S_3") (pintype "passive"))
      (node (ref "M4") (pin "1") (pinfunction "S_1") (pintype "passive"))
      (node (ref "M4") (pin "2") (pinfunction "S_2") (pintype "passive"))
      (node (ref "M4") (pin "3") (pinfunction "S_3") (pintype "passive"))
      (node (ref "R19") (pin "1") (pinfunction "1_1") (pintype "passive"))
      (node (ref "R23") (pin "1") (pinfunction "1_1") (pintype "passive"))
      (node (ref "R26") (pin "2") (pinfunction "2_2") (pintype "passive"))
      (node (ref "R27") (pin "1") (pinfunction "1_1") (pintype "passive"))
      (node (ref "R6") (pin "1") (pinfunction "1_1") (pintype "passive"))
      (node (ref "R7") (pin "1") (pinfunction "1_1") (pintype "passive"))
      (node (ref "R8") (pin "1") (pinfunction "1_1") (pintype "passive"))
      (node (ref "R9") (pin "1") (pinfunction "1_1") (pintype "passive"))
      (node (ref "RT1") (pin "2") (pinfunction "2_2") (pintype "passive"))
      (node (ref "U1") (pin "3") (pinfunction "A_3") (pintype "passive"))
    )
    (net (code "17") (name "Net-(C11-Pad1)") (class "Default")
      (node (ref "C11") (pin "1") (pinfunction "1_1") (pintype "passive"))
      (node (ref "C16") (pin "1") (pinfunction "1_1") (pintype "passive"))
      (node (ref "C17") (pin "1") (pinfunction "1_1") (pintype "passive"))
      (node (ref "C18") (pin "1") (pinfunction "1_1") (pintype "passive"))
      (node (ref "P2") (pin "2") (pinfunction "2_2") (pintype "passive"))
    )
    (net (code "18") (name "Net-(C23-Pad2)") (class "Default")
      (node (ref "C23") (pin "2") (pinfunction "2_2") (pintype "passive"))
      (node (ref "R18") (pin "1") (pinfunction "1_1") (pintype "passive"))
      (node (ref "R19") (pin "2") (pinfunction "2_2") (pintype "passive"))
    )
    (net (code "19") (name "Net-(C33-+)") (class "Default")
      (node (ref "C33") (pin "1") (pinfunction "+_1") (pintype "passive"))
      (node (ref "C34") (pin "2") (pinfunction "2_2") (pintype "passive"))
      (node (ref "IC5") (pin "1") (pinfunction "VIN_1") (pintype "passive"))
      (node (ref "R22") (pin "1") (pinfunction "1_1") (pintype "passive"))
    )
    (net (code "20") (name "Net-(D1-A)") (class "Default")
      (node (ref "D1") (pin "2") (pinfunction "A_2") (pintype "passive"))
      (node (ref "R2") (pin "2") (pinfunction "2_2") (pintype "passive"))
    )
    (net (code "21") (name "Net-(D1-K)") (class "Default")
      (node (ref "D1") (pin "1") (pinfunction "K_1") (pintype "passive"))
      (node (ref "IC1") (pin "7") (pinfunction "HO_7") (pintype "output"))
      (node (ref "R4") (pin "2") (pinfunction "2_2") (pintype "passive"))
      (node (ref "TP2") (pin "1") (pinfunction "TP_1") (pintype "passive"))
    )
    (net (code "22") (name "Net-(D2-A)") (class "Default")
      (node (ref "D2") (pin "2") (pinfunction "A_2") (pintype "passive"))
      (node (ref "R3") (pin "2") (pinfunction "2_2") (pintype "passive"))
    )
    (net (code "23") (name "Net-(D2-K)") (class "Default")
      (node (ref "D2") (pin "1") (pinfunction "K_1") (pintype "passive"))
      (node (ref "IC2") (pin "7") (pinfunction "HO_7") (pintype "output"))
      (node (ref "R5") (pin "2") (pinfunction "2_2") (pintype "passive"))
      (node (ref "TP1") (pin "1") (pinfunction "TP_1") (pintype "passive"))
    )
    (net (code "24") (name "Net-(D3-K)") (class "Default")
      (node (ref "C12") (pin "2") (pinfunction "2_2") (pintype "passive"))
      (node (ref "D3") (pin "1") (pinfunction "K_1") (pintype "passive"))
      (node (ref "IC1") (pin "8") (pinfunction "VB_8") (pintype "power_in"))
    )
    (net (code "25") (name "Net-(D4-K)") (class "Default")
      (node (ref "C13") (pin "2") (pinfunction "2_2") (pintype "passive"))
      (node (ref "D4") (pin "1") (pinfunction "K_1") (pintype "passive"))
      (node (ref "IC2") (pin "8") (pinfunction "VB_8") (pintype "power_in"))
    )
    (net (code "26") (name "Net-(D5-A)") (class "Default")
      (node (ref "D5") (pin "2") (pinfunction "A_2") (pintype "passive"))
      (node (ref "R10") (pin "2") (pinfunction "2_2") (pintype "passive"))
    )
    (net (code "27") (name "Net-(D5-K)") (class "Default")
      (node (ref "D5") (pin "1") (pinfunction "K_1") (pintype "passive"))
      (node (ref "IC1") (pin "5") (pinfunction "LO_5") (pintype "output"))
      (node (ref "R12") (pin "2") (pinfunction "2_2") (pintype "passive"))
      (node (ref "TP7") (pin "1") (pinfunction "TP_1") (pintype "passive"))
    )
    (net (code "28") (name "Net-(D6-A)") (class "Default")
      (node (ref "D6") (pin "2") (pinfunction "A_2") (pintype "passive"))
      (node (ref "R11") (pin "2") (pinfunction "2_2") (pintype "passive"))
    )
    (net (code "29") (name "Net-(D6-K)") (class "Default")
      (node (ref "D6") (pin "1") (pinfunction "K_1") (pintype "passive"))
      (node (ref "IC2") (pin "5") (pinfunction "LO_5") (pintype "output"))
      (node (ref "R13") (pin "2") (pinfunction "2_2") (pintype "passive"))
      (node (ref "TP8") (pin "1") (pinfunction "TP_1") (pintype "passive"))
    )
    (net (code "30") (name "Net-(D7-K)") (class "Default")
      (node (ref "D7") (pin "1") (pinfunction "K_1") (pintype "passive"))
      (node (ref "IC5") (pin "2") (pinfunction "SW_2") (pintype "passive"))
      (node (ref "L1") (pin "1") (pinfunction "1_1") (pintype "passive"))
    )
    (net (code "31") (name "Net-(D8-K)") (class "Default")
      (node (ref "D8") (pin "1") (pinfunction "K_1") (pintype "passive"))
      (node (ref "R26") (pin "1") (pinfunction "1_1") (pintype "passive"))
    )
    (net (code "32") (name "Net-(D9-A)") (class "Default")
      (node (ref "D9") (pin "2") (pinfunction "A_2") (pintype "passive"))
      (node (ref "R25") (pin "1") (pinfunction "1_1") (pintype "passive"))
    )
    (net (code "33") (name "Net-(IC1-VS)") (class "Default")
      (node (ref "C12") (pin "1") (pinfunction "1_1") (pintype "passive"))
      (node (ref "IC1") (pin "6") (pinfunction "VS_6") (pintype "power_in"))
      (node (ref "M1") (pin "1") (pinfunction "S_1") (pintype "passive"))
      (node (ref "M1") (pin "2") (pinfunction "S_2") (pintype "passive"))
      (node (ref "M1") (pin "3") (pinfunction "S_3") (pintype "passive"))
      (node (ref "M3") (pin "5-6-7-8") (pinfunction "D_5-6-7-8") (pintype "passive"))
      (node (ref "P2") (pin "1") (pinfunction "1_1") (pintype "passive"))
      (node (ref "TP6") (pin "1") (pinfunction "TP_1") (pintype "passive"))
    )
    (net (code "34") (name "Net-(IC2-VS)") (class "Default")
      (node (ref "C11") (pin "2") (pinfunction "2_2") (pintype "passive"))
      (node (ref "C13") (pin "1") (pinfunction "1_1") (pintype "passive"))
      (node (ref "C16") (pin "2") (pinfunction "2_2") (pintype "passive"))
      (node (ref "C17") (pin "2") (pinfunction "2_2") (pintype "passive"))
      (node (ref "C18") (pin "2") (pinfunction "2_2") (pintype "passive"))
      (node (ref "IC2") (pin "6") (pinfunction "VS_6") (pintype "power_in"))
      (node (ref "M2") (pin "1") (pinfunction "S_1") (pintype "passive"))
      (node (ref "M2") (pin "2") (pinfunction "S_2") (pintype "passive"))
      (node (ref "M2") (pin "3") (pinfunction "S_3") (pintype "passive"))
      (node (ref "M4") (pin "5-6-7-8") (pinfunction "D_5-6-7-8") (pintype "passive"))
      (node (ref "TP5") (pin "1") (pinfunction "TP_1") (pintype "passive"))
    )
    (net (code "35") (name "Net-(IC3-+IN)") (class "Default")
      (node (ref "C19") (pin "2") (pinfunction "2_2") (pintype "passive"))
      (node (ref "C20") (pin "1") (pinfunction "1_1") (pintype "passive"))
      (node (ref "IC3") (pin "8") (pinfunction "+IN_8") (pintype "passive"))
      (node (ref "R16") (pin "1") (pinfunction "1_1") (pintype "passive"))
    )
    (net (code "36") (name "Net-(IC3--IN)") (class "Default")
      (node (ref "C19") (pin "1") (pinfunction "1_1") (pintype "passive"))
      (node (ref "C21") (pin "2") (pinfunction "2_2") (pintype "passive"))
      (node (ref "IC3") (pin "1") (pinfunction "-IN_1") (pintype "passive"))
      (node (ref "R15") (pin "1") (pinfunction "1_1") (pintype "passive"))
    )
    (net (code "37") (name "Net-(IC5-FB)") (class "Default")
      (node (ref "C36") (pin "1") (pinfunction "1_1") (pintype "passive"))
      (node (ref "IC5") (pin "4") (pinfunction "FB_4") (pintype "passive"))
      (node (ref "R24") (pin "1") (pinfunction "1_1") (pintype "passive"))
      (node (ref "R27") (pin "2") (pinfunction "2_2") (pintype "passive"))
    )
    (net (code "38") (name "Net-(J1-Pad1)") (class "Default")
      (node (ref "J1") (pin "1") (pinfunction "1_1") (pintype "passive"))
      (node (ref "P3") (pin "2") (pinfunction "2_2") (pintype "passive"))
    )
    (net (code "39") (name "Net-(M1-G)") (class "Default")
      (node (ref "M1") (pin "4") (pinfunction "G_4") (pintype "passive"))
      (node (ref "R2") (pin "1") (pinfunction "1_1") (pintype "passive"))
      (node (ref "R4") (pin "1") (pinfunction "1_1") (pintype "passive"))
    )
    (net (code "40") (name "Net-(M2-G)") (class "Default")
      (node (ref "M2") (pin "4") (pinfunction "G_4") (pintype "passive"))
      (node (ref "R3") (pin "1") (pinfunction "1_1") (pintype "passive"))
      (node (ref "R5") (pin "1") (pinfunction "1_1") (pintype "passive"))
    )
    (net (code "41") (name "Net-(M3-G)") (class "Default")
      (node (ref "M3") (pin "4") (pinfunction "G_4") (pintype "passive"))
      (node (ref "R10") (pin "1") (pinfunction "1_1") (pintype "passive"))
      (node (ref "R12") (pin "1") (pinfunction "1_1") (pintype "passive"))
    )
    (net (code "42") (name "Net-(M4-G)") (class "Default")
      (node (ref "M4") (pin "4") (pinfunction "G_4") (pintype "passive"))
      (node (ref "R11") (pin "1") (pinfunction "1_1") (pintype "passive"))
      (node (ref "R13") (pin "1") (pinfunction "1_1") (pintype "passive"))
    )
    (net (code "43") (name "Net-(TP10-TP)") (class "Default")
      (node (ref "C23") (pin "1") (pinfunction "1_1") (pintype "passive"))
      (node (ref "TP10") (pin "1") (pinfunction "TP_1") (pintype "passive"))
      (node (ref "U1") (pin "1") (pinfunction "REF_1") (pintype "input"))
    )
    (net (code "44") (name "unconnected-(IC3-NC_1-Pad3)") (class "Default")
      (node (ref "IC3") (pin "3") (pinfunction "NC_1_3") (pintype "passive+no_connect"))
    )
    (net (code "45") (name "unconnected-(IC3-NC_2-Pad4)") (class "Default")
      (node (ref "IC3") (pin "4") (pinfunction "NC_2_4") (pintype "passive+no_connect"))
    )
    (net (code "46") (name "unconnected-(IC3-NC_3-Pad7)") (class "Default")
      (node (ref "IC3") (pin "7") (pinfunction "NC_3_7") (pintype "passive+no_connect"))
    )
    (net (code "47") (name "unconnected-(J1-Pad2)") (class "Default")
      (node (ref "J1") (pin "2") (pinfunction "2_2") (pintype "passive+no_connect"))
    )
    (net (code "48") (name "unconnected-(J1-Pad3)") (class "Default")
      (node (ref "J1") (pin "3") (pinfunction "3_3") (pintype "passive+no_connect"))
    )
    (net (code "49") (name "unconnected-(J1-Pad4)") (class "Default")
      (node (ref "J1") (pin "4") (pinfunction "4_4") (pintype "passive+no_connect"))
    )
    (net (code "50") (name "unconnected-(J1-Pad5)") (class "Default")
      (node (ref "J1") (pin "5") (pinfunction "5_5") (pintype "passive+no_connect"))
    )
    (net (code "51") (name "unconnected-(J1-Pad6)") (class "Default")
      (node (ref "J1") (pin "6") (pinfunction "6_6") (pintype "passive+no_connect"))
    )
    (net (code "52") (name "unconnected-(J1-Pad7)") (class "Default")
      (node (ref "J1") (pin "7") (pinfunction "7_7") (pintype "passive+no_connect"))
    )
    (net (code "53") (name "unconnected-(J1-Pad10)") (class "Default")
      (node (ref "J1") (pin "10") (pinfunction "10_10") (pintype "passive+no_connect"))
    )
    (net (code "54") (name "unconnected-(J2-Pad2)") (class "Default")
      (node (ref "J2") (pin "2") (pinfunction "2_2") (pintype "passive+no_connect"))
    )
    (net (code "55") (name "unconnected-(J2-Pad5)") (class "Default")
      (node (ref "J2") (pin "5") (pinfunction "5_5") (pintype "passive+no_connect"))
    )
    (net (code "56") (name "unconnected-(J2-Pad6)") (class "Default")
      (node (ref "J2") (pin "6") (pinfunction "6_6") (pintype "passive+no_connect"))
    )
    (net (code "57") (name "unconnected-(J2-Pad7)") (class "Default")
      (node (ref "J2") (pin "7") (pinfunction "7_7") (pintype "passive+no_connect"))
    )
    (net (code "58") (name "unconnected-(M5-Pad1)") (class "Default")
      (node (ref "M5") (pin "1") (pinfunction "1_1") (pintype "passive+no_connect"))
    )
    (net (code "59") (name "unconnected-(M6-Pad1)") (class "Default")
      (node (ref "M6") (pin "1") (pinfunction "1_1") (pintype "passive+no_connect"))
    )
    (net (code "60") (name "unconnected-(M7-Pad1)") (class "Default")
      (node (ref "M7") (pin "1") (pinfunction "1_1") (pintype "passive+no_connect"))
    )
    (net (code "61") (name "unconnected-(M8-Pad1)") (class "Default")
      (node (ref "M8") (pin "1") (pinfunction "1_1") (pintype "passive+no_connect"))
    )
    (net (code "62") (name "unconnected-(P2-SHIELD-PadS1)") (class "Default")
      (node (ref "P2") (pin "S1") (pinfunction "SHIELD_S1") (pintype "passive+no_connect"))
    )
    (net (code "63") (name "unconnected-(P2-SHIELD-PadS2)") (class "Default")
      (node (ref "P2") (pin "S2") (pinfunction "SHIELD_S2") (pintype "passive+no_connect"))
    )
  )
)
